# Signal_Integrity_2L.net
KiCad netlist of a schematic drawn in Altium Designer
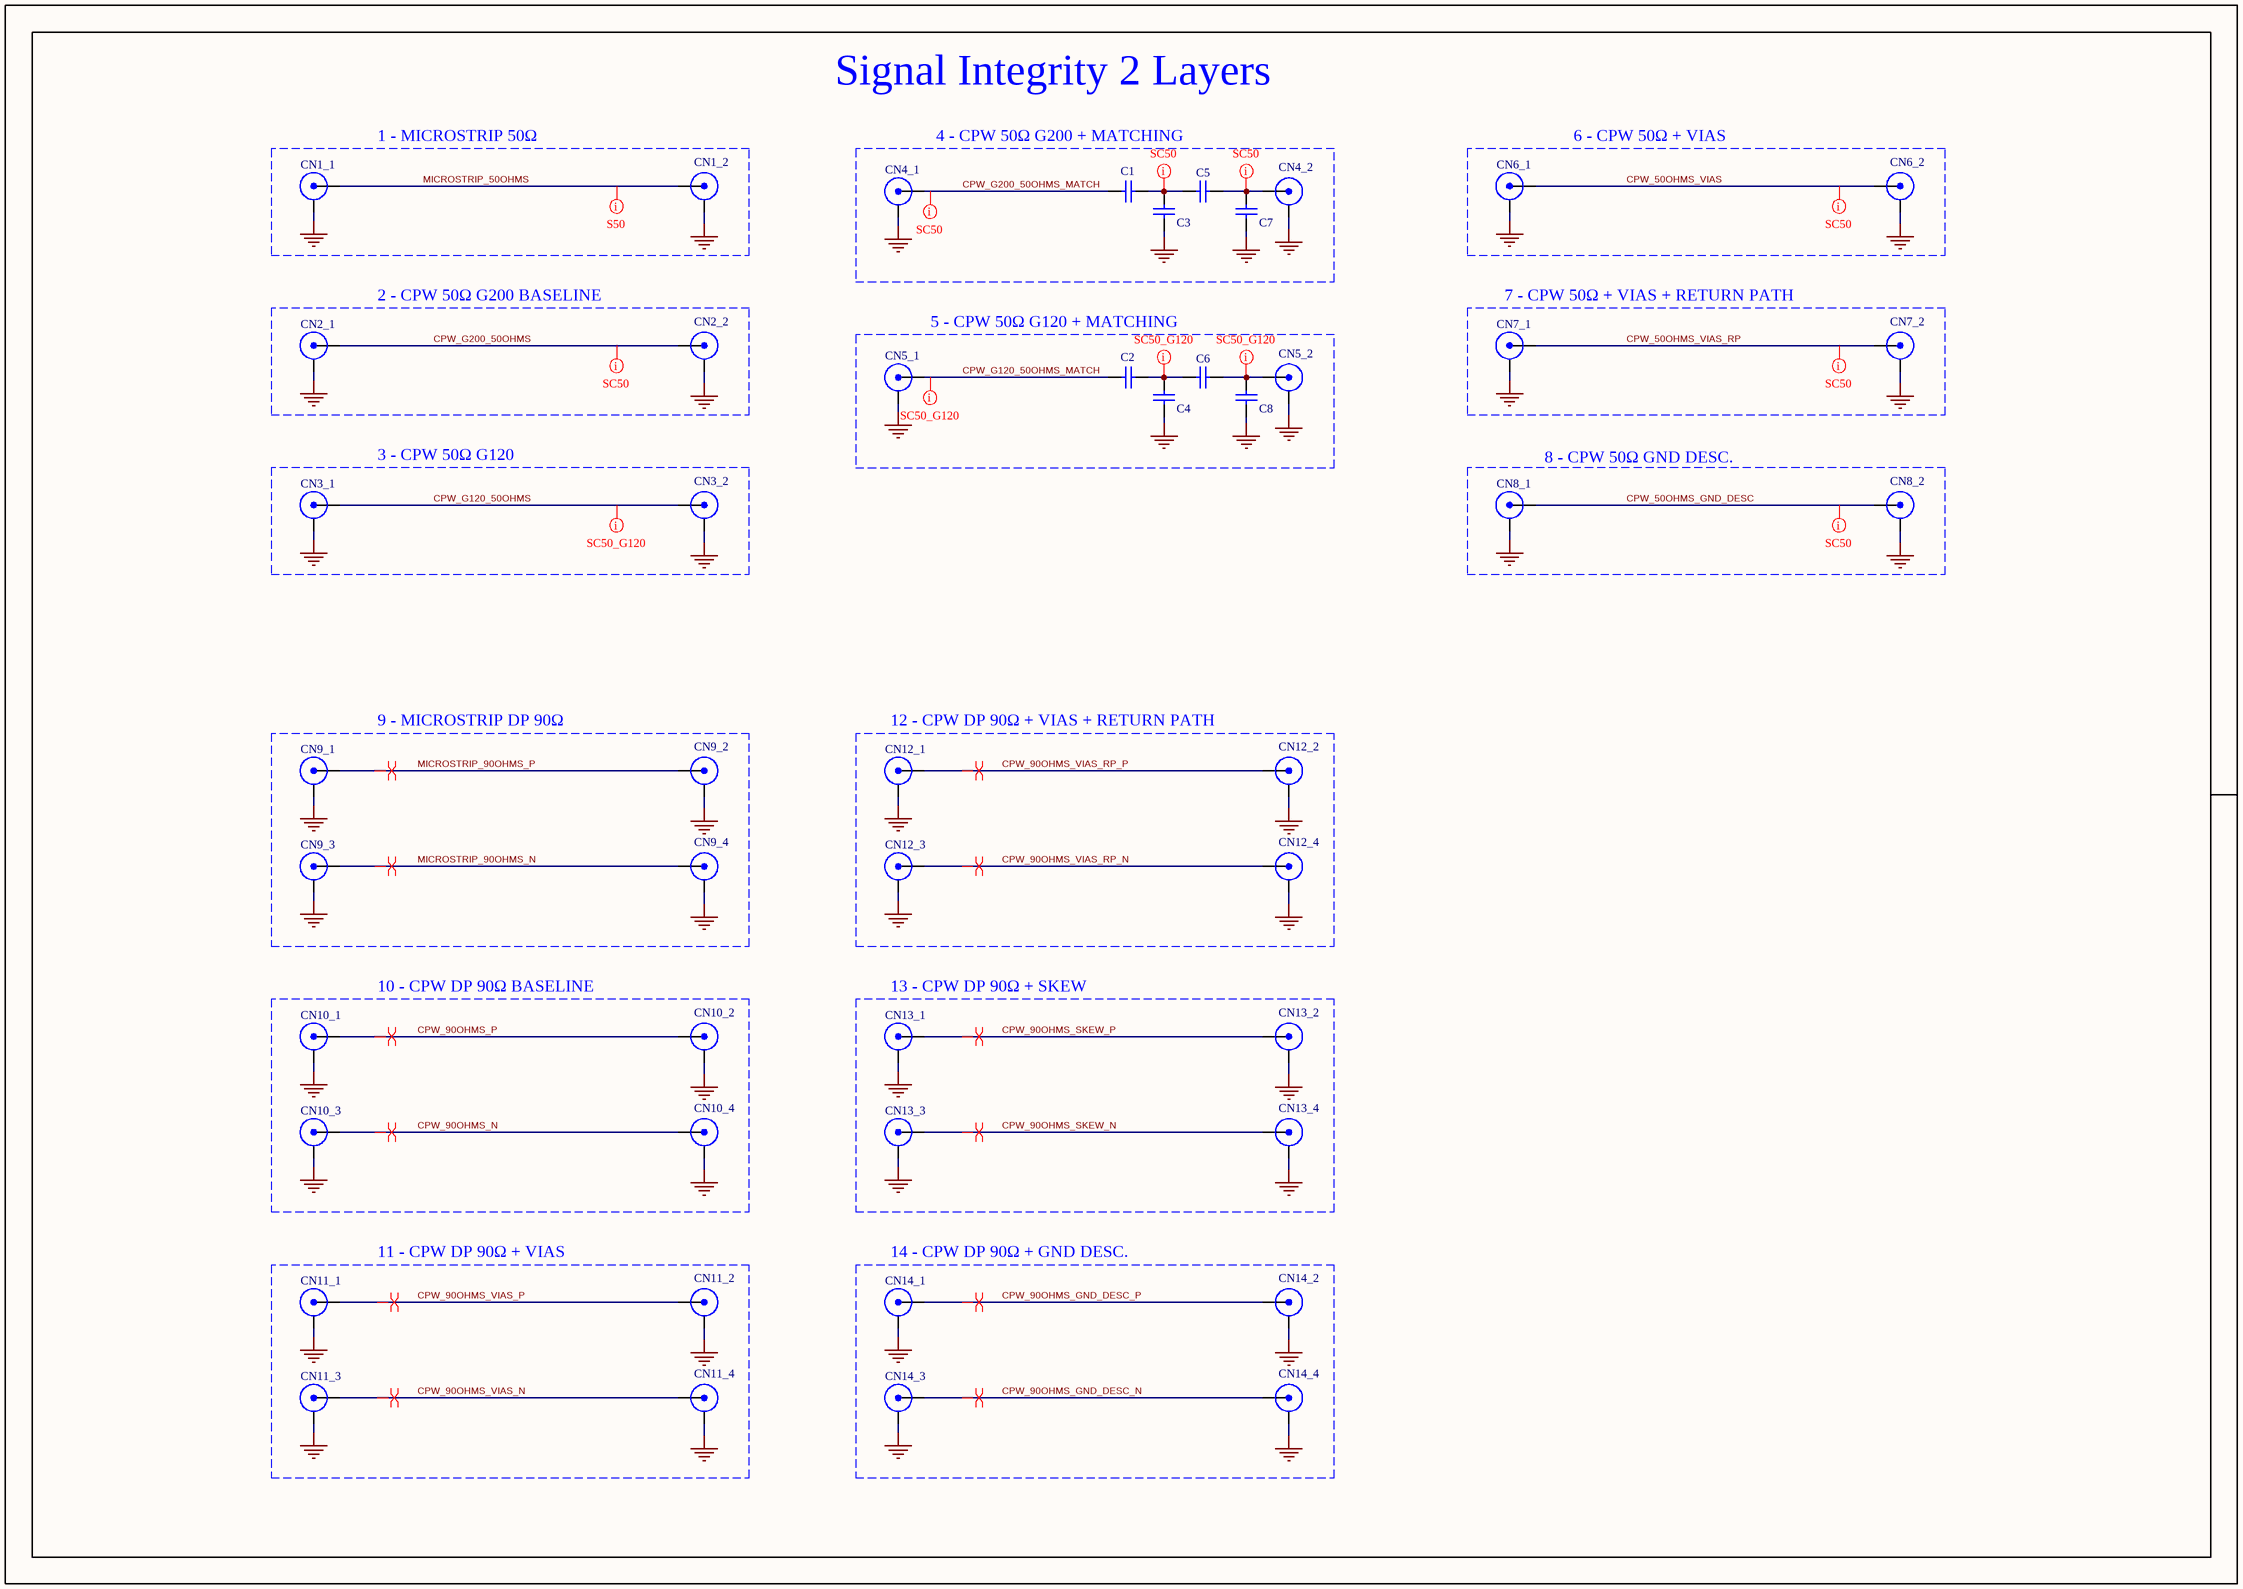
[diagram p0: Signal_Integrity_2L.SchDoc]

(export (version "E")
  (design (tool "Eeschema 10.0.6"))
  (components
    (comp (ref "C1")
      (value "CAP SMD 0402")
      (footprint "0402")
      (description "0402")
      (libsource (lib "Impedance") (part "CAP SMD 0402"))
    )
    (comp (ref "C2")
      (value "CAP SMD 0402")
      (footprint "0402")
      (description "0402")
      (libsource (lib "Impedance") (part "CAP SMD 0402"))
    )
    (comp (ref "C3")
      (value "CAP SMD 0402")
      (footprint "0402")
      (description "0402")
      (libsource (lib "Impedance") (part "CAP SMD 0402"))
    )
    (comp (ref "C4")
      (value "CAP SMD 0402")
      (footprint "0402")
      (description "0402")
      (libsource (lib "Impedance") (part "CAP SMD 0402"))
    )
    (comp (ref "C5")
      (value "CAP SMD 0402")
      (footprint "0402")
      (description "0402")
      (libsource (lib "Impedance") (part "CAP SMD 0402"))
    )
    (comp (ref "C6")
      (value "CAP SMD 0402")
      (footprint "0402")
      (description "0402")
      (libsource (lib "Impedance") (part "CAP SMD 0402"))
    )
    (comp (ref "C7")
      (value "CAP SMD 0402")
      (footprint "0402")
      (description "0402")
      (libsource (lib "Impedance") (part "CAP SMD 0402"))
    )
    (comp (ref "C8")
      (value "CAP SMD 0402")
      (footprint "0402")
      (description "0402")
      (libsource (lib "Impedance") (part "CAP SMD 0402"))
    )
    (comp (ref "CN1_1")
      (value "SMA-KE EDGE")
      (footprint "SMA-KE EDGE")
      (description "SMA Connector Receptacle, Female Socket 50Ohm Board Edge, End Launch Solder")
      (fields
        (field (name "MOUSER PART NUMBER") "712-CONSMA020.062-G")
        (field (name "MANUFACTURER_PART_NUMBER") "CONSMA020.062-G")
      )
      (libsource (lib "Impedance") (part "SMA-KE EDGE"))
    )
    (comp (ref "CN1_2")
      (value "SMA-KE EDGE")
      (footprint "SMA-KE EDGE")
      (description "SMA Connector Receptacle, Female Socket 50Ohm Board Edge, End Launch Solder")
      (fields
        (field (name "MOUSER PART NUMBER") "712-CONSMA020.062-G")
        (field (name "MANUFACTURER_PART_NUMBER") "CONSMA020.062-G")
      )
      (libsource (lib "Impedance") (part "SMA-KE EDGE"))
    )
    (comp (ref "CN2_1")
      (value "SMA-KE EDGE")
      (footprint "SMA-KE EDGE")
      (description "SMA Connector Receptacle, Female Socket 50Ohm Board Edge, End Launch Solder")
      (fields
        (field (name "MOUSER PART NUMBER") "712-CONSMA020.062-G")
        (field (name "MANUFACTURER_PART_NUMBER") "CONSMA020.062-G")
      )
      (libsource (lib "Impedance") (part "SMA-KE EDGE"))
    )
    (comp (ref "CN2_2")
      (value "SMA-KE EDGE")
      (footprint "SMA-KE EDGE")
      (description "SMA Connector Receptacle, Female Socket 50Ohm Board Edge, End Launch Solder")
      (fields
        (field (name "MOUSER PART NUMBER") "712-CONSMA020.062-G")
        (field (name "MANUFACTURER_PART_NUMBER") "CONSMA020.062-G")
      )
      (libsource (lib "Impedance") (part "SMA-KE EDGE"))
    )
    (comp (ref "CN3_1")
      (value "SMA-KE EDGE")
      (footprint "SMA-KE EDGE")
      (description "SMA Connector Receptacle, Female Socket 50Ohm Board Edge, End Launch Solder")
      (fields
        (field (name "MOUSER PART NUMBER") "712-CONSMA020.062-G")
        (field (name "MANUFACTURER_PART_NUMBER") "CONSMA020.062-G")
      )
      (libsource (lib "Impedance") (part "SMA-KE EDGE"))
    )
    (comp (ref "CN3_2")
      (value "SMA-KE EDGE")
      (footprint "SMA-KE EDGE")
      (description "SMA Connector Receptacle, Female Socket 50Ohm Board Edge, End Launch Solder")
      (fields
        (field (name "MOUSER PART NUMBER") "712-CONSMA020.062-G")
        (field (name "MANUFACTURER_PART_NUMBER") "CONSMA020.062-G")
      )
      (libsource (lib "Impedance") (part "SMA-KE EDGE"))
    )
    (comp (ref "CN4_1")
      (value "SMA-KE EDGE")
      (footprint "SMA-KE EDGE")
      (description "SMA Connector Receptacle, Female Socket 50Ohm Board Edge, End Launch Solder")
      (fields
        (field (name "MOUSER PART NUMBER") "712-CONSMA020.062-G")
        (field (name "MANUFACTURER_PART_NUMBER") "CONSMA020.062-G")
      )
      (libsource (lib "Impedance") (part "SMA-KE EDGE"))
    )
    (comp (ref "CN4_2")
      (value "SMA-KE EDGE")
      (footprint "SMA-KE EDGE")
      (description "SMA Connector Receptacle, Female Socket 50Ohm Board Edge, End Launch Solder")
      (fields
        (field (name "MOUSER PART NUMBER") "712-CONSMA020.062-G")
        (field (name "MANUFACTURER_PART_NUMBER") "CONSMA020.062-G")
      )
      (libsource (lib "Impedance") (part "SMA-KE EDGE"))
    )
    (comp (ref "CN5_1")
      (value "SMA-KE EDGE")
      (footprint "SMA-KE EDGE")
      (description "SMA Connector Receptacle, Female Socket 50Ohm Board Edge, End Launch Solder")
      (fields
        (field (name "MOUSER PART NUMBER") "712-CONSMA020.062-G")
        (field (name "MANUFACTURER_PART_NUMBER") "CONSMA020.062-G")
      )
      (libsource (lib "Impedance") (part "SMA-KE EDGE"))
    )
    (comp (ref "CN5_2")
      (value "SMA-KE EDGE")
      (footprint "SMA-KE EDGE")
      (description "SMA Connector Receptacle, Female Socket 50Ohm Board Edge, End Launch Solder")
      (fields
        (field (name "MOUSER PART NUMBER") "712-CONSMA020.062-G")
        (field (name "MANUFACTURER_PART_NUMBER") "CONSMA020.062-G")
      )
      (libsource (lib "Impedance") (part "SMA-KE EDGE"))
    )
    (comp (ref "CN6_1")
      (value "SMA-KE EDGE")
      (footprint "SMA-KE EDGE")
      (description "SMA Connector Receptacle, Female Socket 50Ohm Board Edge, End Launch Solder")
      (fields
        (field (name "MOUSER PART NUMBER") "712-CONSMA020.062-G")
        (field (name "MANUFACTURER_PART_NUMBER") "CONSMA020.062-G")
      )
      (libsource (lib "Impedance") (part "SMA-KE EDGE"))
    )
    (comp (ref "CN6_2")
      (value "SMA-KE EDGE")
      (footprint "SMA-KE EDGE")
      (description "SMA Connector Receptacle, Female Socket 50Ohm Board Edge, End Launch Solder")
      (fields
        (field (name "MOUSER PART NUMBER") "712-CONSMA020.062-G")
        (field (name "MANUFACTURER_PART_NUMBER") "CONSMA020.062-G")
      )
      (libsource (lib "Impedance") (part "SMA-KE EDGE"))
    )
    (comp (ref "CN7_1")
      (value "SMA-KE EDGE")
      (footprint "SMA-KE EDGE")
      (description "SMA Connector Receptacle, Female Socket 50Ohm Board Edge, End Launch Solder")
      (fields
        (field (name "MOUSER PART NUMBER") "712-CONSMA020.062-G")
        (field (name "MANUFACTURER_PART_NUMBER") "CONSMA020.062-G")
      )
      (libsource (lib "Impedance") (part "SMA-KE EDGE"))
    )
    (comp (ref "CN7_2")
      (value "SMA-KE EDGE")
      (footprint "SMA-KE EDGE")
      (description "SMA Connector Receptacle, Female Socket 50Ohm Board Edge, End Launch Solder")
      (fields
        (field (name "MOUSER PART NUMBER") "712-CONSMA020.062-G")
        (field (name "MANUFACTURER_PART_NUMBER") "CONSMA020.062-G")
      )
      (libsource (lib "Impedance") (part "SMA-KE EDGE"))
    )
    (comp (ref "CN8_1")
      (value "SMA-KE EDGE")
      (footprint "SMA-KE EDGE")
      (description "SMA Connector Receptacle, Female Socket 50Ohm Board Edge, End Launch Solder")
      (fields
        (field (name "MOUSER PART NUMBER") "712-CONSMA020.062-G")
        (field (name "MANUFACTURER_PART_NUMBER") "CONSMA020.062-G")
      )
      (libsource (lib "Impedance") (part "SMA-KE EDGE"))
    )
    (comp (ref "CN8_2")
      (value "SMA-KE EDGE")
      (footprint "SMA-KE EDGE")
      (description "SMA Connector Receptacle, Female Socket 50Ohm Board Edge, End Launch Solder")
      (fields
        (field (name "MOUSER PART NUMBER") "712-CONSMA020.062-G")
        (field (name "MANUFACTURER_PART_NUMBER") "CONSMA020.062-G")
      )
      (libsource (lib "Impedance") (part "SMA-KE EDGE"))
    )
    (comp (ref "CN9_1")
      (value "SMA-KE EDGE")
      (footprint "SMA-KE EDGE")
      (description "SMA Connector Receptacle, Female Socket 50Ohm Board Edge, End Launch Solder")
      (fields
        (field (name "MOUSER PART NUMBER") "712-CONSMA020.062-G")
        (field (name "MANUFACTURER_PART_NUMBER") "CONSMA020.062-G")
      )
      (libsource (lib "Impedance") (part "SMA-KE EDGE"))
    )
    (comp (ref "CN9_2")
      (value "SMA-KE EDGE")
      (footprint "SMA-KE EDGE")
      (description "SMA Connector Receptacle, Female Socket 50Ohm Board Edge, End Launch Solder")
      (fields
        (field (name "MOUSER PART NUMBER") "712-CONSMA020.062-G")
        (field (name "MANUFACTURER_PART_NUMBER") "CONSMA020.062-G")
      )
      (libsource (lib "Impedance") (part "SMA-KE EDGE"))
    )
    (comp (ref "CN9_3")
      (value "SMA-KE EDGE")
      (footprint "SMA-KE EDGE")
      (description "SMA Connector Receptacle, Female Socket 50Ohm Board Edge, End Launch Solder")
      (fields
        (field (name "MOUSER PART NUMBER") "712-CONSMA020.062-G")
        (field (name "MANUFACTURER_PART_NUMBER") "CONSMA020.062-G")
      )
      (libsource (lib "Impedance") (part "SMA-KE EDGE"))
    )
    (comp (ref "CN9_4")
      (value "SMA-KE EDGE")
      (footprint "SMA-KE EDGE")
      (description "SMA Connector Receptacle, Female Socket 50Ohm Board Edge, End Launch Solder")
      (fields
        (field (name "MOUSER PART NUMBER") "712-CONSMA020.062-G")
        (field (name "MANUFACTURER_PART_NUMBER") "CONSMA020.062-G")
      )
      (libsource (lib "Impedance") (part "SMA-KE EDGE"))
    )
    (comp (ref "CN10_1")
      (value "SMA-KE EDGE")
      (footprint "SMA-KE EDGE")
      (description "SMA Connector Receptacle, Female Socket 50Ohm Board Edge, End Launch Solder")
      (fields
        (field (name "MOUSER PART NUMBER") "712-CONSMA020.062-G")
        (field (name "MANUFACTURER_PART_NUMBER") "CONSMA020.062-G")
      )
      (libsource (lib "Impedance") (part "SMA-KE EDGE"))
    )
    (comp (ref "CN10_2")
      (value "SMA-KE EDGE")
      (footprint "SMA-KE EDGE")
      (description "SMA Connector Receptacle, Female Socket 50Ohm Board Edge, End Launch Solder")
      (fields
        (field (name "MOUSER PART NUMBER") "712-CONSMA020.062-G")
        (field (name "MANUFACTURER_PART_NUMBER") "CONSMA020.062-G")
      )
      (libsource (lib "Impedance") (part "SMA-KE EDGE"))
    )
    (comp (ref "CN10_3")
      (value "SMA-KE EDGE")
      (footprint "SMA-KE EDGE")
      (description "SMA Connector Receptacle, Female Socket 50Ohm Board Edge, End Launch Solder")
      (fields
        (field (name "MOUSER PART NUMBER") "712-CONSMA020.062-G")
        (field (name "MANUFACTURER_PART_NUMBER") "CONSMA020.062-G")
      )
      (libsource (lib "Impedance") (part "SMA-KE EDGE"))
    )
    (comp (ref "CN10_4")
      (value "SMA-KE EDGE")
      (footprint "SMA-KE EDGE")
      (description "SMA Connector Receptacle, Female Socket 50Ohm Board Edge, End Launch Solder")
      (fields
        (field (name "MOUSER PART NUMBER") "712-CONSMA020.062-G")
        (field (name "MANUFACTURER_PART_NUMBER") "CONSMA020.062-G")
      )
      (libsource (lib "Impedance") (part "SMA-KE EDGE"))
    )
    (comp (ref "CN11_1")
      (value "SMA-KE EDGE")
      (footprint "SMA-KE EDGE")
      (description "SMA Connector Receptacle, Female Socket 50Ohm Board Edge, End Launch Solder")
      (fields
        (field (name "MOUSER PART NUMBER") "712-CONSMA020.062-G")
        (field (name "MANUFACTURER_PART_NUMBER") "CONSMA020.062-G")
      )
      (libsource (lib "Impedance") (part "SMA-KE EDGE"))
    )
    (comp (ref "CN11_2")
      (value "SMA-KE EDGE")
      (footprint "SMA-KE EDGE")
      (description "SMA Connector Receptacle, Female Socket 50Ohm Board Edge, End Launch Solder")
      (fields
        (field (name "MOUSER PART NUMBER") "712-CONSMA020.062-G")
        (field (name "MANUFACTURER_PART_NUMBER") "CONSMA020.062-G")
      )
      (libsource (lib "Impedance") (part "SMA-KE EDGE"))
    )
    (comp (ref "CN11_3")
      (value "SMA-KE EDGE")
      (footprint "SMA-KE EDGE")
      (description "SMA Connector Receptacle, Female Socket 50Ohm Board Edge, End Launch Solder")
      (fields
        (field (name "MOUSER PART NUMBER") "712-CONSMA020.062-G")
        (field (name "MANUFACTURER_PART_NUMBER") "CONSMA020.062-G")
      )
      (libsource (lib "Impedance") (part "SMA-KE EDGE"))
    )
    (comp (ref "CN11_4")
      (value "SMA-KE EDGE")
      (footprint "SMA-KE EDGE")
      (description "SMA Connector Receptacle, Female Socket 50Ohm Board Edge, End Launch Solder")
      (fields
        (field (name "MOUSER PART NUMBER") "712-CONSMA020.062-G")
        (field (name "MANUFACTURER_PART_NUMBER") "CONSMA020.062-G")
      )
      (libsource (lib "Impedance") (part "SMA-KE EDGE"))
    )
    (comp (ref "CN12_1")
      (value "SMA-KE EDGE")
      (footprint "SMA-KE EDGE")
      (description "SMA Connector Receptacle, Female Socket 50Ohm Board Edge, End Launch Solder")
      (fields
        (field (name "MOUSER PART NUMBER") "712-CONSMA020.062-G")
        (field (name "MANUFACTURER_PART_NUMBER") "CONSMA020.062-G")
      )
      (libsource (lib "Impedance") (part "SMA-KE EDGE"))
    )
    (comp (ref "CN12_2")
      (value "SMA-KE EDGE")
      (footprint "SMA-KE EDGE")
      (description "SMA Connector Receptacle, Female Socket 50Ohm Board Edge, End Launch Solder")
      (fields
        (field (name "MOUSER PART NUMBER") "712-CONSMA020.062-G")
        (field (name "MANUFACTURER_PART_NUMBER") "CONSMA020.062-G")
      )
      (libsource (lib "Impedance") (part "SMA-KE EDGE"))
    )
    (comp (ref "CN12_3")
      (value "SMA-KE EDGE")
      (footprint "SMA-KE EDGE")
      (description "SMA Connector Receptacle, Female Socket 50Ohm Board Edge, End Launch Solder")
      (fields
        (field (name "MOUSER PART NUMBER") "712-CONSMA020.062-G")
        (field (name "MANUFACTURER_PART_NUMBER") "CONSMA020.062-G")
      )
      (libsource (lib "Impedance") (part "SMA-KE EDGE"))
    )
    (comp (ref "CN12_4")
      (value "SMA-KE EDGE")
      (footprint "SMA-KE EDGE")
      (description "SMA Connector Receptacle, Female Socket 50Ohm Board Edge, End Launch Solder")
      (fields
        (field (name "MOUSER PART NUMBER") "712-CONSMA020.062-G")
        (field (name "MANUFACTURER_PART_NUMBER") "CONSMA020.062-G")
      )
      (libsource (lib "Impedance") (part "SMA-KE EDGE"))
    )
    (comp (ref "CN13_1")
      (value "SMA-KE EDGE")
      (footprint "SMA-KE EDGE")
      (description "SMA Connector Receptacle, Female Socket 50Ohm Board Edge, End Launch Solder")
      (fields
        (field (name "MOUSER PART NUMBER") "712-CONSMA020.062-G")
        (field (name "MANUFACTURER_PART_NUMBER") "CONSMA020.062-G")
      )
      (libsource (lib "Impedance") (part "SMA-KE EDGE"))
    )
    (comp (ref "CN13_2")
      (value "SMA-KE EDGE")
      (footprint "SMA-KE EDGE")
      (description "SMA Connector Receptacle, Female Socket 50Ohm Board Edge, End Launch Solder")
      (fields
        (field (name "MOUSER PART NUMBER") "712-CONSMA020.062-G")
        (field (name "MANUFACTURER_PART_NUMBER") "CONSMA020.062-G")
      )
      (libsource (lib "Impedance") (part "SMA-KE EDGE"))
    )
    (comp (ref "CN13_3")
      (value "SMA-KE EDGE")
      (footprint "SMA-KE EDGE")
      (description "SMA Connector Receptacle, Female Socket 50Ohm Board Edge, End Launch Solder")
      (fields
        (field (name "MOUSER PART NUMBER") "712-CONSMA020.062-G")
        (field (name "MANUFACTURER_PART_NUMBER") "CONSMA020.062-G")
      )
      (libsource (lib "Impedance") (part "SMA-KE EDGE"))
    )
    (comp (ref "CN13_4")
      (value "SMA-KE EDGE")
      (footprint "SMA-KE EDGE")
      (description "SMA Connector Receptacle, Female Socket 50Ohm Board Edge, End Launch Solder")
      (fields
        (field (name "MOUSER PART NUMBER") "712-CONSMA020.062-G")
        (field (name "MANUFACTURER_PART_NUMBER") "CONSMA020.062-G")
      )
      (libsource (lib "Impedance") (part "SMA-KE EDGE"))
    )
    (comp (ref "CN14_1")
      (value "SMA-KE EDGE")
      (footprint "SMA-KE EDGE")
      (description "SMA Connector Receptacle, Female Socket 50Ohm Board Edge, End Launch Solder")
      (fields
        (field (name "MOUSER PART NUMBER") "712-CONSMA020.062-G")
        (field (name "MANUFACTURER_PART_NUMBER") "CONSMA020.062-G")
      )
      (libsource (lib "Impedance") (part "SMA-KE EDGE"))
    )
    (comp (ref "CN14_2")
      (value "SMA-KE EDGE")
      (footprint "SMA-KE EDGE")
      (description "SMA Connector Receptacle, Female Socket 50Ohm Board Edge, End Launch Solder")
      (fields
        (field (name "MOUSER PART NUMBER") "712-CONSMA020.062-G")
        (field (name "MANUFACTURER_PART_NUMBER") "CONSMA020.062-G")
      )
      (libsource (lib "Impedance") (part "SMA-KE EDGE"))
    )
    (comp (ref "CN14_3")
      (value "SMA-KE EDGE")
      (footprint "SMA-KE EDGE")
      (description "SMA Connector Receptacle, Female Socket 50Ohm Board Edge, End Launch Solder")
      (fields
        (field (name "MOUSER PART NUMBER") "712-CONSMA020.062-G")
        (field (name "MANUFACTURER_PART_NUMBER") "CONSMA020.062-G")
      )
      (libsource (lib "Impedance") (part "SMA-KE EDGE"))
    )
    (comp (ref "CN14_4")
      (value "SMA-KE EDGE")
      (footprint "SMA-KE EDGE")
      (description "SMA Connector Receptacle, Female Socket 50Ohm Board Edge, End Launch Solder")
      (fields
        (field (name "MOUSER PART NUMBER") "712-CONSMA020.062-G")
        (field (name "MANUFACTURER_PART_NUMBER") "CONSMA020.062-G")
      )
      (libsource (lib "Impedance") (part "SMA-KE EDGE"))
    )
  )
  (nets
    (net (code "1") (name "/CPW_50OHMS_GND_DESC") (class "Default")
      (node (ref "CN8_1") (pin "1") (pinfunction "SIGNAL_1") (pintype "passive"))
      (node (ref "CN8_2") (pin "1") (pinfunction "SIGNAL_1") (pintype "passive"))
    )
    (net (code "2") (name "/CPW_50OHMS_VIAS") (class "Default")
      (node (ref "CN6_1") (pin "1") (pinfunction "SIGNAL_1") (pintype "passive"))
      (node (ref "CN6_2") (pin "1") (pinfunction "SIGNAL_1") (pintype "passive"))
    )
    (net (code "3") (name "/CPW_50OHMS_VIAS_RP") (class "Default")
      (node (ref "CN7_1") (pin "1") (pinfunction "SIGNAL_1") (pintype "passive"))
      (node (ref "CN7_2") (pin "1") (pinfunction "SIGNAL_1") (pintype "passive"))
    )
    (net (code "4") (name "/CPW_90OHMS_GND_DESC_N") (class "Default")
      (node (ref "CN14_3") (pin "1") (pinfunction "SIGNAL_1") (pintype "passive"))
      (node (ref "CN14_4") (pin "1") (pinfunction "SIGNAL_1") (pintype "passive"))
    )
    (net (code "5") (name "/CPW_90OHMS_GND_DESC_P") (class "Default")
      (node (ref "CN14_1") (pin "1") (pinfunction "SIGNAL_1") (pintype "passive"))
      (node (ref "CN14_2") (pin "1") (pinfunction "SIGNAL_1") (pintype "passive"))
    )
    (net (code "6") (name "/CPW_90OHMS_N") (class "Default")
      (node (ref "CN10_3") (pin "1") (pinfunction "SIGNAL_1") (pintype "passive"))
      (node (ref "CN10_4") (pin "1") (pinfunction "SIGNAL_1") (pintype "passive"))
    )
    (net (code "7") (name "/CPW_90OHMS_P") (class "Default")
      (node (ref "CN10_1") (pin "1") (pinfunction "SIGNAL_1") (pintype "passive"))
      (node (ref "CN10_2") (pin "1") (pinfunction "SIGNAL_1") (pintype "passive"))
    )
    (net (code "8") (name "/CPW_90OHMS_SKEW_N") (class "Default")
      (node (ref "CN13_3") (pin "1") (pinfunction "SIGNAL_1") (pintype "passive"))
      (node (ref "CN13_4") (pin "1") (pinfunction "SIGNAL_1") (pintype "passive"))
    )
    (net (code "9") (name "/CPW_90OHMS_SKEW_P") (class "Default")
      (node (ref "CN13_1") (pin "1") (pinfunction "SIGNAL_1") (pintype "passive"))
      (node (ref "CN13_2") (pin "1") (pinfunction "SIGNAL_1") (pintype "passive"))
    )
    (net (code "10") (name "/CPW_90OHMS_VIAS_N") (class "Default")
      (node (ref "CN11_3") (pin "1") (pinfunction "SIGNAL_1") (pintype "passive"))
      (node (ref "CN11_4") (pin "1") (pinfunction "SIGNAL_1") (pintype "passive"))
    )
    (net (code "11") (name "/CPW_90OHMS_VIAS_P") (class "Default")
      (node (ref "CN11_1") (pin "1") (pinfunction "SIGNAL_1") (pintype "passive"))
      (node (ref "CN11_2") (pin "1") (pinfunction "SIGNAL_1") (pintype "passive"))
    )
    (net (code "12") (name "/CPW_90OHMS_VIAS_RP_N") (class "Default")
      (node (ref "CN12_3") (pin "1") (pinfunction "SIGNAL_1") (pintype "passive"))
      (node (ref "CN12_4") (pin "1") (pinfunction "SIGNAL_1") (pintype "passive"))
    )
    (net (code "13") (name "/CPW_90OHMS_VIAS_RP_P") (class "Default")
      (node (ref "CN12_1") (pin "1") (pinfunction "SIGNAL_1") (pintype "passive"))
      (node (ref "CN12_2") (pin "1") (pinfunction "SIGNAL_1") (pintype "passive"))
    )
    (net (code "14") (name "/CPW_G120_50OHMS") (class "Default")
      (node (ref "CN3_1") (pin "1") (pinfunction "SIGNAL_1") (pintype "passive"))
      (node (ref "CN3_2") (pin "1") (pinfunction "SIGNAL_1") (pintype "passive"))
    )
    (net (code "15") (name "/CPW_G120_50OHMS_MATCH") (class "Default")
      (node (ref "C2") (pin "1") (pinfunction "1_1") (pintype "passive"))
      (node (ref "CN5_1") (pin "1") (pinfunction "SIGNAL_1") (pintype "passive"))
    )
    (net (code "16") (name "/CPW_G200_50OHMS") (class "Default")
      (node (ref "CN2_1") (pin "1") (pinfunction "SIGNAL_1") (pintype "passive"))
      (node (ref "CN2_2") (pin "1") (pinfunction "SIGNAL_1") (pintype "passive"))
    )
    (net (code "17") (name "/CPW_G200_50OHMS_MATCH") (class "Default")
      (node (ref "C1") (pin "1") (pinfunction "1_1") (pintype "passive"))
      (node (ref "CN4_1") (pin "1") (pinfunction "SIGNAL_1") (pintype "passive"))
    )
    (net (code "18") (name "/MICROSTRIP_50OHMS") (class "Default")
      (node (ref "CN1_1") (pin "1") (pinfunction "SIGNAL_1") (pintype "passive"))
      (node (ref "CN1_2") (pin "1") (pinfunction "SIGNAL_1") (pintype "passive"))
    )
    (net (code "19") (name "/MICROSTRIP_90OHMS_N") (class "Default")
      (node (ref "CN9_3") (pin "1") (pinfunction "SIGNAL_1") (pintype "passive"))
      (node (ref "CN9_4") (pin "1") (pinfunction "SIGNAL_1") (pintype "passive"))
    )
    (net (code "20") (name "/MICROSTRIP_90OHMS_P") (class "Default")
      (node (ref "CN9_1") (pin "1") (pinfunction "SIGNAL_1") (pintype "passive"))
      (node (ref "CN9_2") (pin "1") (pinfunction "SIGNAL_1") (pintype "passive"))
    )
    (net (code "21") (name "GND1") (class "Default")
      (node (ref "CN1_1") (pin "2") (pinfunction "GND_2") (pintype "passive"))
      (node (ref "CN1_2") (pin "2") (pinfunction "GND_2") (pintype "passive"))
    )
    (net (code "22") (name "GND2") (class "Default")
      (node (ref "CN2_1") (pin "2") (pinfunction "GND_2") (pintype "passive"))
      (node (ref "CN2_2") (pin "2") (pinfunction "GND_2") (pintype "passive"))
    )
    (net (code "23") (name "GND3") (class "Default")
      (node (ref "CN3_1") (pin "2") (pinfunction "GND_2") (pintype "passive"))
      (node (ref "CN3_2") (pin "2") (pinfunction "GND_2") (pintype "passive"))
    )
    (net (code "24") (name "GND4") (class "Default")
      (node (ref "C3") (pin "1") (pinfunction "1_1") (pintype "passive"))
      (node (ref "C7") (pin "1") (pinfunction "1_1") (pintype "passive"))
      (node (ref "CN4_1") (pin "2") (pinfunction "GND_2") (pintype "passive"))
      (node (ref "CN4_2") (pin "2") (pinfunction "GND_2") (pintype "passive"))
    )
    (net (code "25") (name "GND5") (class "Default")
      (node (ref "C4") (pin "1") (pinfunction "1_1") (pintype "passive"))
      (node (ref "C8") (pin "1") (pinfunction "1_1") (pintype "passive"))
      (node (ref "CN5_1") (pin "2") (pinfunction "GND_2") (pintype "passive"))
      (node (ref "CN5_2") (pin "2") (pinfunction "GND_2") (pintype "passive"))
    )
    (net (code "26") (name "GND6") (class "Default")
      (node (ref "CN6_1") (pin "2") (pinfunction "GND_2") (pintype "passive"))
      (node (ref "CN6_2") (pin "2") (pinfunction "GND_2") (pintype "passive"))
    )
    (net (code "27") (name "GND7") (class "Default")
      (node (ref "CN7_1") (pin "2") (pinfunction "GND_2") (pintype "passive"))
      (node (ref "CN7_2") (pin "2") (pinfunction "GND_2") (pintype "passive"))
    )
    (net (code "28") (name "GND8") (class "Default")
      (node (ref "CN8_1") (pin "2") (pinfunction "GND_2") (pintype "passive"))
      (node (ref "CN8_2") (pin "2") (pinfunction "GND_2") (pintype "passive"))
    )
    (net (code "29") (name "GND9") (class "Default")
      (node (ref "CN9_1") (pin "2") (pinfunction "GND_2") (pintype "passive"))
      (node (ref "CN9_2") (pin "2") (pinfunction "GND_2") (pintype "passive"))
      (node (ref "CN9_3") (pin "2") (pinfunction "GND_2") (pintype "passive"))
      (node (ref "CN9_4") (pin "2") (pinfunction "GND_2") (pintype "passive"))
    )
    (net (code "30") (name "GND10") (class "Default")
      (node (ref "CN10_1") (pin "2") (pinfunction "GND_2") (pintype "passive"))
      (node (ref "CN10_2") (pin "2") (pinfunction "GND_2") (pintype "passive"))
      (node (ref "CN10_3") (pin "2") (pinfunction "GND_2") (pintype "passive"))
      (node (ref "CN10_4") (pin "2") (pinfunction "GND_2") (pintype "passive"))
    )
    (net (code "31") (name "GND11") (class "Default")
      (node (ref "CN11_1") (pin "2") (pinfunction "GND_2") (pintype "passive"))
      (node (ref "CN11_2") (pin "2") (pinfunction "GND_2") (pintype "passive"))
      (node (ref "CN11_3") (pin "2") (pinfunction "GND_2") (pintype "passive"))
      (node (ref "CN11_4") (pin "2") (pinfunction "GND_2") (pintype "passive"))
    )
    (net (code "32") (name "GND12") (class "Default")
      (node (ref "CN12_1") (pin "2") (pinfunction "GND_2") (pintype "passive"))
      (node (ref "CN12_2") (pin "2") (pinfunction "GND_2") (pintype "passive"))
      (node (ref "CN12_3") (pin "2") (pinfunction "GND_2") (pintype "passive"))
      (node (ref "CN12_4") (pin "2") (pinfunction "GND_2") (pintype "passive"))
    )
    (net (code "33") (name "GND13") (class "Default")
      (node (ref "CN13_1") (pin "2") (pinfunction "GND_2") (pintype "passive"))
      (node (ref "CN13_2") (pin "2") (pinfunction "GND_2") (pintype "passive"))
      (node (ref "CN13_3") (pin "2") (pinfunction "GND_2") (pintype "passive"))
      (node (ref "CN13_4") (pin "2") (pinfunction "GND_2") (pintype "passive"))
    )
    (net (code "34") (name "GND14") (class "Default")
      (node (ref "CN14_1") (pin "2") (pinfunction "GND_2") (pintype "passive"))
      (node (ref "CN14_2") (pin "2") (pinfunction "GND_2") (pintype "passive"))
      (node (ref "CN14_3") (pin "2") (pinfunction "GND_2") (pintype "passive"))
      (node (ref "CN14_4") (pin "2") (pinfunction "GND_2") (pintype "passive"))
    )
    (net (code "35") (name "Net-(C1-Pad2)") (class "Default")
      (node (ref "C1") (pin "2") (pinfunction "2_2") (pintype "passive"))
      (node (ref "C3") (pin "2") (pinfunction "2_2") (pintype "passive"))
      (node (ref "C5") (pin "1") (pinfunction "1_1") (pintype "passive"))
    )
    (net (code "36") (name "Net-(C2-Pad2)") (class "Default")
      (node (ref "C2") (pin "2") (pinfunction "2_2") (pintype "passive"))
      (node (ref "C4") (pin "2") (pinfunction "2_2") (pintype "passive"))
      (node (ref "C6") (pin "1") (pinfunction "1_1") (pintype "passive"))
    )
    (net (code "37") (name "Net-(CN4_2-SIGNAL)") (class "Default")
      (node (ref "C5") (pin "2") (pinfunction "2_2") (pintype "passive"))
      (node (ref "C7") (pin "2") (pinfunction "2_2") (pintype "passive"))
      (node (ref "CN4_2") (pin "1") (pinfunction "SIGNAL_1") (pintype "passive"))
    )
    (net (code "38") (name "Net-(CN5_2-SIGNAL)") (class "Default")
      (node (ref "C6") (pin "2") (pinfunction "2_2") (pintype "passive"))
      (node (ref "C8") (pin "2") (pinfunction "2_2") (pintype "passive"))
      (node (ref "CN5_2") (pin "1") (pinfunction "SIGNAL_1") (pintype "passive"))
    )
  )
)
